# USB_interface.net
KiCad netlist of a schematic drawn in Altium Designer
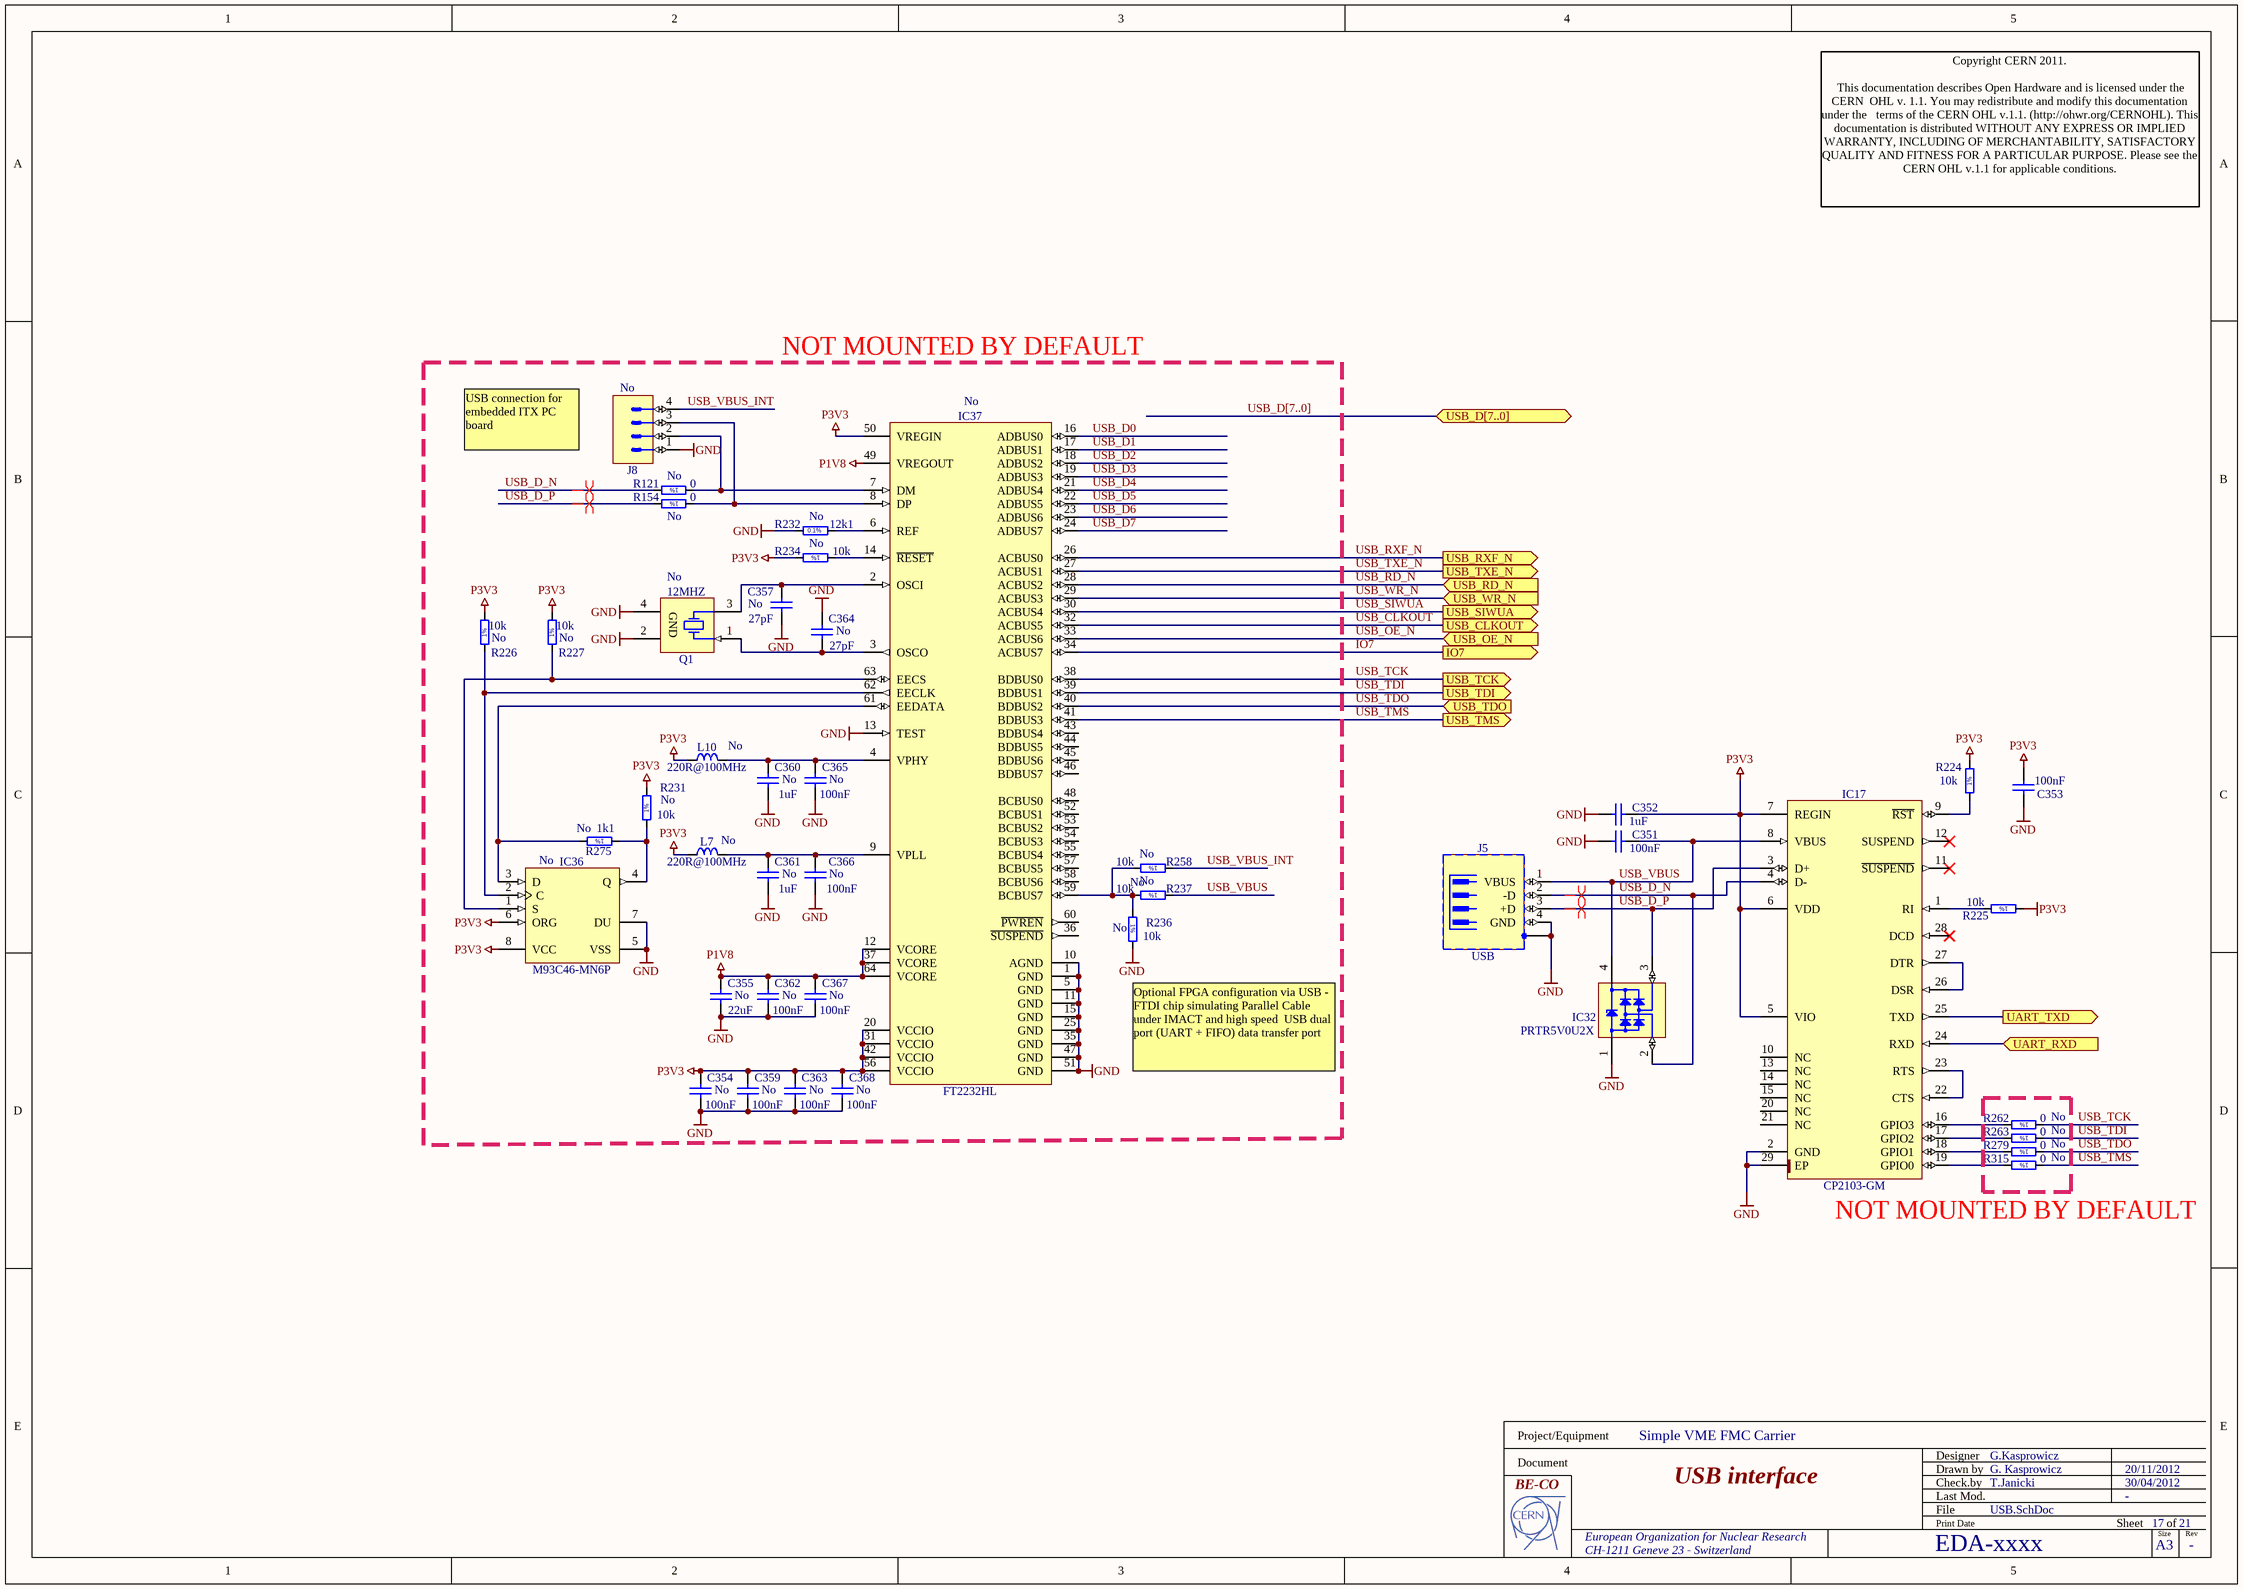
[diagram p0: USB_interface.SchDoc]

(export (version "E")
  (design (tool "Eeschema 10.0.6"))
  (components
    (comp (ref "C351")
      (value "100nF")
      (footprint "CAPC1005X55N")
      (description "Non-polarised capacitor")
      (fields
        (field (name "PART NUMBER") "CC0402_100NF_16V_10%_X7R")
        (field (name "VOLTAGE") "16V")
        (field (name "AUTHOR") "CERN DEM JLC")
      )
      (libsource (lib "Capacitors") (part "Capacitor - non polarized"))
    )
    (comp (ref "C352")
      (value "1uF")
      (footprint "CAPC1608X87N")
      (description "Non-polarised capacitor")
      (fields
        (field (name "PART NUMBER") "CC0603_1UF_16V_10%_X7R")
        (field (name "VOLTAGE") "16V")
        (field (name "AUTHOR") "CERN DEM JLC")
      )
      (libsource (lib "Capacitors") (part "Capacitor - non polarized"))
    )
    (comp (ref "C353")
      (value "100nF")
      (footprint "CAPC1005X55N")
      (description "Non-polarised capacitor")
      (fields
        (field (name "PART NUMBER") "CC0402_100NF_16V_10%_X7R")
        (field (name "VOLTAGE") "16V")
        (field (name "AUTHOR") "CERN DEM JLC")
      )
      (libsource (lib "Capacitors") (part "Capacitor - non polarized"))
    )
    (comp (ref "C354")
      (value "100nF")
      (footprint "CAPC1005X55N")
      (description "Non-polarised capacitor")
      (fields
        (field (name "PART NUMBER") "CC0402_100NF_16V_10%_X7R")
        (field (name "VOLTAGE") "16V")
        (field (name "MOUNTED") "No")
        (field (name "AUTHOR") "CERN DEM JLC")
      )
      (libsource (lib "Capacitors") (part "Capacitor - non polarized"))
    )
    (comp (ref "C355")
      (value "22uF")
      (footprint "CAPC3216X180N")
      (description "Non-polarised capacitor")
      (fields
        (field (name "PART NUMBER") "CC1206_22UF_10V_10%_X7R")
        (field (name "VOLTAGE") "10V")
        (field (name "MOUNTED") "No")
        (field (name "AUTHOR") "CERN DEM JLC")
      )
      (libsource (lib "Capacitors") (part "Capacitor - non polarized"))
    )
    (comp (ref "C357")
      (value "27pF")
      (footprint "CAPC1608X87N")
      (description "Non-polarised capacitor")
      (fields
        (field (name "PART NUMBER") "CC0603_27PF_50V_5%_NP0")
        (field (name "VOLTAGE") "50V")
        (field (name "MOUNTED") "No")
        (field (name "AUTHOR") "CERN DEM JLC")
      )
      (libsource (lib "Capacitors") (part "Capacitor - non polarized"))
    )
    (comp (ref "C359")
      (value "100nF")
      (footprint "CAPC1005X55N")
      (description "Non-polarised capacitor")
      (fields
        (field (name "PART NUMBER") "CC0402_100NF_16V_10%_X7R")
        (field (name "VOLTAGE") "16V")
        (field (name "MOUNTED") "No")
        (field (name "AUTHOR") "CERN DEM JLC")
      )
      (libsource (lib "Capacitors") (part "Capacitor - non polarized"))
    )
    (comp (ref "C360")
      (value "1uF")
      (footprint "CAPC1608X87N")
      (description "Non-polarised capacitor")
      (fields
        (field (name "PART NUMBER") "CC0603_1UF_16V_10%_X7R")
        (field (name "VOLTAGE") "16V")
        (field (name "MOUNTED") "No")
        (field (name "AUTHOR") "CERN DEM JLC")
      )
      (libsource (lib "Capacitors") (part "Capacitor - non polarized"))
    )
    (comp (ref "C361")
      (value "1uF")
      (footprint "CAPC1608X87N")
      (description "Non-polarised capacitor")
      (fields
        (field (name "PART NUMBER") "CC0603_1UF_16V_10%_X7R")
        (field (name "VOLTAGE") "16V")
        (field (name "MOUNTED") "No")
        (field (name "AUTHOR") "CERN DEM JLC")
      )
      (libsource (lib "Capacitors") (part "Capacitor - non polarized"))
    )
    (comp (ref "C362")
      (value "100nF")
      (footprint "CAPC1005X55N")
      (description "Non-polarised capacitor")
      (fields
        (field (name "PART NUMBER") "CC0402_100NF_16V_10%_X7R")
        (field (name "VOLTAGE") "16V")
        (field (name "MOUNTED") "No")
        (field (name "AUTHOR") "CERN DEM JLC")
      )
      (libsource (lib "Capacitors") (part "Capacitor - non polarized"))
    )
    (comp (ref "C363")
      (value "100nF")
      (footprint "CAPC1005X55N")
      (description "Non-polarised capacitor")
      (fields
        (field (name "PART NUMBER") "CC0402_100NF_16V_10%_X7R")
        (field (name "VOLTAGE") "16V")
        (field (name "MOUNTED") "No")
        (field (name "AUTHOR") "CERN DEM JLC")
      )
      (libsource (lib "Capacitors") (part "Capacitor - non polarized"))
    )
    (comp (ref "C364")
      (value "27pF")
      (footprint "CAPC1608X87N")
      (description "Non-polarised capacitor")
      (fields
        (field (name "PART NUMBER") "CC0603_27PF_50V_5%_NP0")
        (field (name "VOLTAGE") "50V")
        (field (name "MOUNTED") "No")
        (field (name "AUTHOR") "CERN DEM JLC")
      )
      (libsource (lib "Capacitors") (part "Capacitor - non polarized"))
    )
    (comp (ref "C365")
      (value "100nF")
      (footprint "CAPC1005X55N")
      (description "Non-polarised capacitor")
      (fields
        (field (name "PART NUMBER") "CC0402_100NF_16V_10%_X7R")
        (field (name "VOLTAGE") "16V")
        (field (name "MOUNTED") "No")
        (field (name "AUTHOR") "CERN DEM JLC")
      )
      (libsource (lib "Capacitors") (part "Capacitor - non polarized"))
    )
    (comp (ref "C366")
      (value "100nF")
      (footprint "CAPC1005X55N")
      (description "Non-polarised capacitor")
      (fields
        (field (name "PART NUMBER") "CC0402_100NF_16V_10%_X7R")
        (field (name "VOLTAGE") "16V")
        (field (name "MOUNTED") "No")
        (field (name "AUTHOR") "CERN DEM JLC")
      )
      (libsource (lib "Capacitors") (part "Capacitor - non polarized"))
    )
    (comp (ref "C367")
      (value "100nF")
      (footprint "CAPC1005X55N")
      (description "Non-polarised capacitor")
      (fields
        (field (name "PART NUMBER") "CC0402_100NF_16V_10%_X7R")
        (field (name "VOLTAGE") "16V")
        (field (name "MOUNTED") "No")
        (field (name "AUTHOR") "CERN DEM JLC")
      )
      (libsource (lib "Capacitors") (part "Capacitor - non polarized"))
    )
    (comp (ref "C368")
      (value "100nF")
      (footprint "CAPC1005X55N")
      (description "Non-polarised capacitor")
      (fields
        (field (name "PART NUMBER") "CC0402_100NF_16V_10%_X7R")
        (field (name "VOLTAGE") "16V")
        (field (name "MOUNTED") "No")
        (field (name "AUTHOR") "CERN DEM JLC")
      )
      (libsource (lib "Capacitors") (part "Capacitor - non polarized"))
    )
    (comp (ref "IC17")
      (value "CP2103-GM")
      (footprint "QFN50P500X500X100-29N-S335")
      (description "Single-Chip USB to UART Bridge")
      (fields (field (name "MANUFACTURER") "SILICON LABS") (field (name "AUTHOR") "CERN DEM JLC"))
      (libsource (lib "ICs And Semiconductors") (part "CP2103-GM"))
    )
    (comp (ref "IC32")
      (value "PRTR5V0U2X")
      (footprint "SOT190P230X110-4N")
      (description "Ultra Low Capacitance Double Rail-to-Rail ESD Protection Diode")
      (fields
        (field (name "VOLTAGE") "5.5V")
        (field (name "MANUFACTURER") "PHILIPS NXP")
        (field (name "AUTHOR") "CERN DEM JLC")
      )
      (libsource (lib "ICs And Semiconductors") (part "PRTR5V0U2X"))
    )
    (comp (ref "IC36")
      (value "M93C46-MN6P")
      (footprint "SOIC127P600X175-8N")
      (description "1Kb (x8/x16) Serial Microwire Bus EEPROM")
      (fields
        (field (name "MANUFACTURER") "ST MICROELECTRONICS")
        (field (name "MOUNTED") "No")
        (field (name "AUTHOR") "CERN DEM JLC")
      )
      (libsource (lib "ICs And Semiconductors") (part "M93C46-MN"))
    )
    (comp (ref "IC37")
      (value "FT2232HL")
      (footprint "QFP50P1200X1200X160-64N")
      (description "Dual High Speed USB to Multipurpose UART/FIFO IC")
      (fields
        (field (name "MANUFACTURER") "FUTURE TECHNOLOGY DEVICES INTERNATIONAL (FTDI)")
        (field (name "MOUNTED") "No")
        (field (name "AUTHOR") "CERN DEM JLC")
      )
      (libsource (lib "ICs And Semiconductors") (part "FT2232H"))
    )
    (comp (ref "J5")
      (value "USB")
      (footprint "TYCO_292304-1")
      (description "4 Pin + 1 Shield USB Receptacle")
      (fields
        (field (name "PART NUMBER") "TYCO_292304-1")
        (field (name "MANUFACTURER") "TYCO ELECTRONICS")
        (field (name "AUTHOR") "CERN DEM JLC")
      )
      (libsource (lib "Connectors") (part "Connector USB 4 Pin + 1Shield"))
    )
    (comp (ref "J8")
      (value "KK®")
      (footprint "MOLEX_22-04-1041")
      (description "Connector 4 Male")
      (fields
        (field (name "PART NUMBER") "MOLEX_22-04-1041")
        (field (name "MOUNTED") "No")
        (field (name "MANUFACTURER") "MOLEX")
        (field (name "AUTHOR") "CERN DEM JLC")
      )
      (libsource (lib "Connectors") (part "Connector 4 Male"))
    )
    (comp (ref "L7")
      (value "220R@100MHz")
      (footprint "INDC2012X105N")
      (description "Inductor")
      (fields
        (field (name "PART NUMBER") "IND0805_MURATA_BLM21PG221SN1D")
        (field (name "POWER") "2A")
        (field (name "MOUNTED") "No")
        (field (name "AUTHOR") "CERN DEM JLC")
      )
      (libsource (lib "Inductors & Transformers") (part "Inductor"))
    )
    (comp (ref "L10")
      (value "220R@100MHz")
      (footprint "INDC2012X105N")
      (description "Inductor")
      (fields
        (field (name "PART NUMBER") "IND0805_MURATA_BLM21PG221SN1D")
        (field (name "POWER") "2A")
        (field (name "MOUNTED") "No")
        (field (name "AUTHOR") "CERN DEM JLC")
      )
      (libsource (lib "Inductors & Transformers") (part "Inductor"))
    )
    (comp (ref "Q1")
      (value "12MHZ")
      (footprint "XTAL_ABRACON_ABM3B")
      (description "Crystal 4 pins 1=XTAL Control 2=GND3=XTAL 4=GND")
      (fields
        (field (name "PART NUMBER") "XTAL_12MHZ_ABRACON_ABM3B-12.000MHZ-B2-T")
        (field (name "MANUFACTURER") "ABRACON")
        (field (name "MOUNTED") "No")
        (field (name "AUTHOR") "CERN DEM JLC")
      )
      (libsource (lib "ICs And Semiconductors") (part "Quartz Crystal 1X 2GND 3X 4GND"))
    )
    (comp (ref "R121")
      (value "0")
      (footprint "RESC1608X55N")
      (description "Resistor - 1%")
      (fields
        (field (name "PART NUMBER") "R0603_0R_JUMPER")
        (field (name "MANUFACTURER") "GENERIC")
        (field (name "MOUNTED") "No")
        (field (name "AUTHOR") "CERN DEM JLC")
      )
      (libsource (lib "Resistors") (part "Resistor - 1%"))
    )
    (comp (ref "R154")
      (value "0")
      (footprint "RESC1608X55N")
      (description "Resistor - 1%")
      (fields
        (field (name "PART NUMBER") "R0603_0R_JUMPER")
        (field (name "MANUFACTURER") "GENERIC")
        (field (name "MOUNTED") "No")
        (field (name "AUTHOR") "CERN DEM JLC")
      )
      (libsource (lib "Resistors") (part "Resistor - 1%"))
    )
    (comp (ref "R224")
      (value "10k")
      (footprint "RESC1608X55N")
      (description "Resistor - 1%")
      (fields
        (field (name "PART NUMBER") "R0603_10K_1%_0.1W_100PPM")
        (field (name "POWER") "0.1W")
        (field (name "AUTHOR") "CERN DEM JLC")
      )
      (libsource (lib "Resistors") (part "Resistor - 1%"))
    )
    (comp (ref "R225")
      (value "10k")
      (footprint "RESC1608X55N")
      (description "Resistor - 1%")
      (fields
        (field (name "PART NUMBER") "R0603_10K_1%_0.1W_100PPM")
        (field (name "POWER") "0.1W")
        (field (name "AUTHOR") "CERN DEM JLC")
      )
      (libsource (lib "Resistors") (part "Resistor - 1%"))
    )
    (comp (ref "R226")
      (value "10k")
      (footprint "RESC1608X55N")
      (description "Resistor - 1%")
      (fields
        (field (name "PART NUMBER") "R0603_10K_1%_0.1W_100PPM")
        (field (name "POWER") "0.1W")
        (field (name "MOUNTED") "No")
        (field (name "AUTHOR") "CERN DEM JLC")
      )
      (libsource (lib "Resistors") (part "Resistor - 1%"))
    )
    (comp (ref "R227")
      (value "10k")
      (footprint "RESC1608X55N")
      (description "Resistor - 1%")
      (fields
        (field (name "PART NUMBER") "R0603_10K_1%_0.1W_100PPM")
        (field (name "POWER") "0.1W")
        (field (name "MOUNTED") "No")
        (field (name "AUTHOR") "CERN DEM JLC")
      )
      (libsource (lib "Resistors") (part "Resistor - 1%"))
    )
    (comp (ref "R231")
      (value "10k")
      (footprint "RESC1608X55N")
      (description "Resistor - 1%")
      (fields
        (field (name "PART NUMBER") "R0603_10K_1%_0.1W_100PPM")
        (field (name "POWER") "0.1W")
        (field (name "MOUNTED") "No")
        (field (name "AUTHOR") "CERN DEM JLC")
      )
      (libsource (lib "Resistors") (part "Resistor - 1%"))
    )
    (comp (ref "R232")
      (value "12k1")
      (footprint "RESC1608X55N")
      (description "Resistor - 0.1%")
      (fields
        (field (name "PART NUMBER") "R0603_12K1_0.1%_0.063W_10PPM")
        (field (name "POWER") "0.063W")
        (field (name "MOUNTED") "No")
        (field (name "AUTHOR") "CERN DEM JLC")
      )
      (libsource (lib "Resistors") (part "Resistor - 0.1%"))
    )
    (comp (ref "R234")
      (value "10k")
      (footprint "RESC1608X55N")
      (description "Resistor - 1%")
      (fields
        (field (name "PART NUMBER") "R0603_10K_1%_0.1W_100PPM")
        (field (name "POWER") "0.1W")
        (field (name "MOUNTED") "No")
        (field (name "AUTHOR") "CERN DEM JLC")
      )
      (libsource (lib "Resistors") (part "Resistor - 1%"))
    )
    (comp (ref "R236")
      (value "10k")
      (footprint "RESC1608X55N")
      (description "Resistor - 1%")
      (fields
        (field (name "PART NUMBER") "R0603_10K_1%_0.1W_100PPM")
        (field (name "POWER") "0.1W")
        (field (name "MOUNTED") "No")
        (field (name "AUTHOR") "CERN DEM JLC")
      )
      (libsource (lib "Resistors") (part "Resistor - 1%"))
    )
    (comp (ref "R237")
      (value "10k")
      (footprint "RESC1608X55N")
      (description "Resistor - 1%")
      (fields
        (field (name "PART NUMBER") "R0603_10K_1%_0.1W_100PPM")
        (field (name "POWER") "0.1W")
        (field (name "MOUNTED") "No")
        (field (name "SOCKET") "No")
        (field (name "AUTHOR") "CERN DEM JLC")
      )
      (libsource (lib "Resistors") (part "Resistor - 1%"))
    )
    (comp (ref "R258")
      (value "10k")
      (footprint "RESC1608X55N")
      (description "Resistor - 1%")
      (fields
        (field (name "PART NUMBER") "R0603_10K_1%_0.1W_100PPM")
        (field (name "POWER") "0.1W")
        (field (name "MOUNTED") "No")
        (field (name "AUTHOR") "CERN DEM JLC")
      )
      (libsource (lib "Resistors") (part "Resistor - 1%"))
    )
    (comp (ref "R262")
      (value "0")
      (footprint "RESC1608X55N")
      (description "Resistor - 1%")
      (fields
        (field (name "PART NUMBER") "R0603_0R_JUMPER")
        (field (name "MANUFACTURER") "GENERIC")
        (field (name "MOUNTED") "No")
        (field (name "AUTHOR") "CERN DEM JLC")
      )
      (libsource (lib "Resistors") (part "Resistor - 1%"))
    )
    (comp (ref "R263")
      (value "0")
      (footprint "RESC1608X55N")
      (description "Resistor - 1%")
      (fields
        (field (name "PART NUMBER") "R0603_0R_JUMPER")
        (field (name "MANUFACTURER") "GENERIC")
        (field (name "MOUNTED") "No")
        (field (name "AUTHOR") "CERN DEM JLC")
      )
      (libsource (lib "Resistors") (part "Resistor - 1%"))
    )
    (comp (ref "R275")
      (value "1k1")
      (footprint "RESC1608X55N")
      (description "Resistor - 1%")
      (fields
        (field (name "PART NUMBER") "R0603_1K1_1%_0.1W_100PPM")
        (field (name "POWER") "0.1W")
        (field (name "MOUNTED") "No")
        (field (name "AUTHOR") "CERN DEM JLC")
      )
      (libsource (lib "Resistors") (part "Resistor - 1%"))
    )
    (comp (ref "R279")
      (value "0")
      (footprint "RESC1608X55N")
      (description "Resistor - 1%")
      (fields
        (field (name "PART NUMBER") "R0603_0R_JUMPER")
        (field (name "MANUFACTURER") "GENERIC")
        (field (name "MOUNTED") "No")
        (field (name "AUTHOR") "CERN DEM JLC")
      )
      (libsource (lib "Resistors") (part "Resistor - 1%"))
    )
    (comp (ref "R315")
      (value "0")
      (footprint "RESC1608X55N")
      (description "Resistor - 1%")
      (fields
        (field (name "PART NUMBER") "R0603_0R_JUMPER")
        (field (name "MANUFACTURER") "GENERIC")
        (field (name "MOUNTED") "No")
        (field (name "AUTHOR") "CERN DEM JLC")
      )
      (libsource (lib "Resistors") (part "Resistor - 1%"))
    )
  )
  (nets
    (net (code "1") (name "/IO7") (class "Default")
      (node (ref "IC37") (pin "34") (pinfunction "ACBUS7_34") (pintype "bidirectional"))
    )
    (net (code "2") (name "/UART_RXD") (class "Default")
      (node (ref "IC17") (pin "24") (pinfunction "RXD_24") (pintype "input"))
    )
    (net (code "3") (name "/UART_TXD") (class "Default")
      (node (ref "IC17") (pin "25") (pinfunction "TXD_25") (pintype "output"))
    )
    (net (code "4") (name "/USB_CLKOUT") (class "Default")
      (node (ref "IC37") (pin "32") (pinfunction "ACBUS5_32") (pintype "bidirectional"))
    )
    (net (code "5") (name "/USB_D0") (class "Default")
      (node (ref "IC37") (pin "16") (pinfunction "ADBUS0_16") (pintype "bidirectional"))
    )
    (net (code "6") (name "/USB_D1") (class "Default")
      (node (ref "IC37") (pin "17") (pinfunction "ADBUS1_17") (pintype "bidirectional"))
    )
    (net (code "7") (name "/USB_D2") (class "Default")
      (node (ref "IC37") (pin "18") (pinfunction "ADBUS2_18") (pintype "bidirectional"))
    )
    (net (code "8") (name "/USB_D3") (class "Default")
      (node (ref "IC37") (pin "19") (pinfunction "ADBUS3_19") (pintype "bidirectional"))
    )
    (net (code "9") (name "/USB_D4") (class "Default")
      (node (ref "IC37") (pin "21") (pinfunction "ADBUS4_21") (pintype "bidirectional"))
    )
    (net (code "10") (name "/USB_D5") (class "Default")
      (node (ref "IC37") (pin "22") (pinfunction "ADBUS5_22") (pintype "bidirectional"))
    )
    (net (code "11") (name "/USB_D6") (class "Default")
      (node (ref "IC37") (pin "23") (pinfunction "ADBUS6_23") (pintype "bidirectional"))
    )
    (net (code "12") (name "/USB_D7") (class "Default")
      (node (ref "IC37") (pin "24") (pinfunction "ADBUS7_24") (pintype "bidirectional"))
    )
    (net (code "14") (name "/USB_D_N") (class "Default")
      (node (ref "IC17") (pin "4") (pinfunction "D-_4") (pintype "bidirectional"))
      (node (ref "IC32") (pin "2") (pinfunction "I/O1_2") (pintype "bidirectional"))
      (node (ref "J5") (pin "2") (pinfunction "-D_2") (pintype "bidirectional"))
      (node (ref "R121") (pin "2") (pinfunction "2_2") (pintype "passive"))
    )
    (net (code "15") (name "/USB_D_P") (class "Default")
      (node (ref "IC17") (pin "3") (pinfunction "D+_3") (pintype "bidirectional"))
      (node (ref "IC32") (pin "3") (pinfunction "I/O2_3") (pintype "bidirectional"))
      (node (ref "J5") (pin "3") (pinfunction "+D_3") (pintype "bidirectional"))
      (node (ref "R154") (pin "2") (pinfunction "2_2") (pintype "passive"))
    )
    (net (code "16") (name "/USB_OE_N") (class "Default")
      (node (ref "IC37") (pin "33") (pinfunction "ACBUS6_33") (pintype "bidirectional"))
    )
    (net (code "17") (name "/USB_RD_N") (class "Default")
      (node (ref "IC37") (pin "28") (pinfunction "ACBUS2_28") (pintype "bidirectional"))
    )
    (net (code "18") (name "/USB_RXF_N") (class "Default")
      (node (ref "IC37") (pin "26") (pinfunction "ACBUS0_26") (pintype "bidirectional"))
    )
    (net (code "19") (name "/USB_SIWUA") (class "Default")
      (node (ref "IC37") (pin "30") (pinfunction "ACBUS4_30") (pintype "bidirectional"))
    )
    (net (code "20") (name "/USB_TCK") (class "Default")
      (node (ref "IC37") (pin "38") (pinfunction "BDBUS0_38") (pintype "bidirectional"))
      (node (ref "R262") (pin "1") (pinfunction "1_1") (pintype "passive"))
    )
    (net (code "21") (name "/USB_TDI") (class "Default")
      (node (ref "IC37") (pin "39") (pinfunction "BDBUS1_39") (pintype "bidirectional"))
      (node (ref "R263") (pin "1") (pinfunction "1_1") (pintype "passive"))
    )
    (net (code "22") (name "/USB_TDO") (class "Default")
      (node (ref "IC37") (pin "40") (pinfunction "BDBUS2_40") (pintype "bidirectional"))
      (node (ref "R279") (pin "1") (pinfunction "1_1") (pintype "passive"))
    )
    (net (code "23") (name "/USB_TMS") (class "Default")
      (node (ref "IC37") (pin "41") (pinfunction "BDBUS3_41") (pintype "bidirectional"))
      (node (ref "R315") (pin "1") (pinfunction "1_1") (pintype "passive"))
    )
    (net (code "24") (name "/USB_TXE_N") (class "Default")
      (node (ref "IC37") (pin "27") (pinfunction "ACBUS1_27") (pintype "bidirectional"))
    )
    (net (code "25") (name "/USB_VBUS") (class "Default")
      (node (ref "C351") (pin "1") (pinfunction "1_1") (pintype "passive"))
      (node (ref "IC17") (pin "8") (pinfunction "VBUS_8") (pintype "input"))
      (node (ref "IC32") (pin "4") (pinfunction "VCC_4") (pintype "power_in"))
      (node (ref "J5") (pin "1") (pinfunction "VBUS_1") (pintype "bidirectional"))
      (node (ref "R237") (pin "1") (pinfunction "1_1") (pintype "passive"))
    )
    (net (code "26") (name "/USB_VBUS_INT") (class "Default")
      (node (ref "J8") (pin "4") (pinfunction "4_4") (pintype "bidirectional"))
      (node (ref "R258") (pin "1") (pinfunction "1_1") (pintype "passive"))
    )
    (net (code "27") (name "/USB_WR_N") (class "Default")
      (node (ref "IC37") (pin "29") (pinfunction "ACBUS3_29") (pintype "bidirectional"))
    )
    (net (code "28") (name "GND") (class "Default")
      (node (ref "C351") (pin "2") (pinfunction "2_2") (pintype "passive"))
      (node (ref "C352") (pin "2") (pinfunction "2_2") (pintype "passive"))
      (node (ref "C353") (pin "2") (pinfunction "2_2") (pintype "passive"))
      (node (ref "C354") (pin "2") (pinfunction "2_2") (pintype "passive"))
      (node (ref "C355") (pin "1") (pinfunction "1_1") (pintype "passive"))
      (node (ref "C357") (pin "1") (pinfunction "1_1") (pintype "passive"))
      (node (ref "C359") (pin "2") (pinfunction "2_2") (pintype "passive"))
      (node (ref "C360") (pin "1") (pinfunction "1_1") (pintype "passive"))
      (node (ref "C361") (pin "1") (pinfunction "1_1") (pintype "passive"))
      (node (ref "C362") (pin "2") (pinfunction "2_2") (pintype "passive"))
      (node (ref "C363") (pin "2") (pinfunction "2_2") (pintype "passive"))
      (node (ref "C364") (pin "1") (pinfunction "1_1") (pintype "passive"))
      (node (ref "C365") (pin "2") (pinfunction "2_2") (pintype "passive"))
      (node (ref "C366") (pin "2") (pinfunction "2_2") (pintype "passive"))
      (node (ref "C367") (pin "2") (pinfunction "2_2") (pintype "passive"))
      (node (ref "C368") (pin "2") (pinfunction "2_2") (pintype "passive"))
      (node (ref "IC17") (pin "2") (pinfunction "GND_2") (pintype "power_in"))
      (node (ref "IC17") (pin "29") (pinfunction "EP_29") (pintype "power_in"))
      (node (ref "IC32") (pin "1") (pinfunction "GND_1") (pintype "power_in"))
      (node (ref "IC36") (pin "5") (pinfunction "VSS_5") (pintype "power_in"))
      (node (ref "IC36") (pin "7") (pinfunction "DU_7") (pintype "passive"))
      (node (ref "IC37") (pin "1") (pinfunction "GND_1") (pintype "power_in"))
      (node (ref "IC37") (pin "10") (pinfunction "AGND_10") (pintype "power_in"))
      (node (ref "IC37") (pin "11") (pinfunction "GND_11") (pintype "power_in"))
      (node (ref "IC37") (pin "13") (pinfunction "TEST_13") (pintype "input"))
      (node (ref "IC37") (pin "15") (pinfunction "GND_15") (pintype "power_in"))
      (node (ref "IC37") (pin "25") (pinfunction "GND_25") (pintype "power_in"))
      (node (ref "IC37") (pin "35") (pinfunction "GND_35") (pintype "power_in"))
      (node (ref "IC37") (pin "47") (pinfunction "GND_47") (pintype "power_in"))
      (node (ref "IC37") (pin "5") (pinfunction "GND_5") (pintype "power_in"))
      (node (ref "IC37") (pin "51") (pinfunction "GND_51") (pintype "power_in"))
      (node (ref "J5") (pin "4") (pinfunction "GND_4") (pintype "bidirectional"))
      (node (ref "J5") (pin "5") (pinfunction "SH_5") (pintype "power_in"))
      (node (ref "J8") (pin "1") (pinfunction "1_1") (pintype "bidirectional"))
      (node (ref "Q1") (pin "2") (pinfunction "GND_2") (pintype "power_in"))
      (node (ref "Q1") (pin "4") (pinfunction "GND_4") (pintype "power_in"))
      (node (ref "R232") (pin "1") (pinfunction "1_1") (pintype "passive"))
      (node (ref "R236") (pin "2") (pinfunction "2_2") (pintype "passive"))
    )
    (net (code "29") (name "Net-(IC17-CTS)") (class "Default")
      (node (ref "IC17") (pin "22") (pinfunction "CTS_22") (pintype "input"))
      (node (ref "IC17") (pin "23") (pinfunction "RTS_23") (pintype "output"))
    )
    (net (code "30") (name "Net-(IC17-DSR)") (class "Default")
      (node (ref "IC17") (pin "26") (pinfunction "DSR_26") (pintype "input"))
      (node (ref "IC17") (pin "27") (pinfunction "DTR_27") (pintype "output"))
    )
    (net (code "31") (name "Net-(IC17-GPIO0)") (class "Default")
      (node (ref "IC17") (pin "19") (pinfunction "GPIO0_19") (pintype "bidirectional"))
      (node (ref "R315") (pin "2") (pinfunction "2_2") (pintype "passive"))
    )
    (net (code "32") (name "Net-(IC17-GPIO1)") (class "Default")
      (node (ref "IC17") (pin "18") (pinfunction "GPIO1_18") (pintype "bidirectional"))
      (node (ref "R279") (pin "2") (pinfunction "2_2") (pintype "passive"))
    )
    (net (code "33") (name "Net-(IC17-GPIO2)") (class "Default")
      (node (ref "IC17") (pin "17") (pinfunction "GPIO2_17") (pintype "bidirectional"))
      (node (ref "R263") (pin "2") (pinfunction "2_2") (pintype "passive"))
    )
    (net (code "34") (name "Net-(IC17-GPIO3)") (class "Default")
      (node (ref "IC17") (pin "16") (pinfunction "GPIO3_16") (pintype "bidirectional"))
      (node (ref "R262") (pin "2") (pinfunction "2_2") (pintype "passive"))
    )
    (net (code "35") (name "Net-(IC17-RI)") (class "Default")
      (node (ref "IC17") (pin "1") (pinfunction "RI_1") (pintype "input"))
      (node (ref "R225") (pin "2") (pinfunction "2_2") (pintype "passive"))
    )
    (net (code "36") (name "Net-(IC17-~{RST})") (class "Default")
      (node (ref "IC17") (pin "9") (pinfunction "~{RST}_9") (pintype "bidirectional"))
      (node (ref "R224") (pin "1") (pinfunction "1_1") (pintype "passive"))
    )
    (net (code "37") (name "Net-(IC36-C)") (class "Default")
      (node (ref "IC36") (pin "2") (pinfunction "C_2") (pintype "input"))
      (node (ref "IC37") (pin "62") (pinfunction "EECLK_62") (pintype "output"))
      (node (ref "R226") (pin "1") (pinfunction "1_1") (pintype "passive"))
    )
    (net (code "38") (name "Net-(IC36-D)") (class "Default")
      (node (ref "IC36") (pin "3") (pinfunction "D_3") (pintype "input"))
      (node (ref "IC37") (pin "61") (pinfunction "EEDATA_61") (pintype "bidirectional"))
      (node (ref "R275") (pin "2") (pinfunction "2_2") (pintype "passive"))
    )
    (net (code "39") (name "Net-(IC36-Q)") (class "Default")
      (node (ref "IC36") (pin "4") (pinfunction "Q_4") (pintype "output"))
      (node (ref "R231") (pin "1") (pinfunction "1_1") (pintype "passive"))
      (node (ref "R275") (pin "1") (pinfunction "1_1") (pintype "passive"))
    )
    (net (code "40") (name "Net-(IC36-S)") (class "Default")
      (node (ref "IC36") (pin "1") (pinfunction "S_1") (pintype "input"))
      (node (ref "IC37") (pin "63") (pinfunction "EECS_63") (pintype "bidirectional"))
      (node (ref "R227") (pin "1") (pinfunction "1_1") (pintype "passive"))
    )
    (net (code "41") (name "Net-(IC37-BCBUS7)") (class "Default")
      (node (ref "IC37") (pin "59") (pinfunction "BCBUS7_59") (pintype "bidirectional"))
      (node (ref "R236") (pin "1") (pinfunction "1_1") (pintype "passive"))
      (node (ref "R237") (pin "2") (pinfunction "2_2") (pintype "passive"))
      (node (ref "R258") (pin "2") (pinfunction "2_2") (pintype "passive"))
    )
    (net (code "42") (name "Net-(IC37-DM)") (class "Default")
      (node (ref "IC37") (pin "7") (pinfunction "DM_7") (pintype "input"))
      (node (ref "J8") (pin "2") (pinfunction "2_2") (pintype "bidirectional"))
      (node (ref "R121") (pin "1") (pinfunction "1_1") (pintype "passive"))
    )
    (net (code "43") (name "Net-(IC37-DP)") (class "Default")
      (node (ref "IC37") (pin "8") (pinfunction "DP_8") (pintype "input"))
      (node (ref "J8") (pin "3") (pinfunction "3_3") (pintype "bidirectional"))
      (node (ref "R154") (pin "1") (pinfunction "1_1") (pintype "passive"))
    )
    (net (code "44") (name "Net-(IC37-OSCI)") (class "Default")
      (node (ref "C357") (pin "2") (pinfunction "2_2") (pintype "passive"))
      (node (ref "IC37") (pin "2") (pinfunction "OSCI_2") (pintype "input"))
      (node (ref "Q1") (pin "3") (pinfunction "X_3") (pintype "power_in"))
    )
    (net (code "45") (name "Net-(IC37-OSCO)") (class "Default")
      (node (ref "C364") (pin "2") (pinfunction "2_2") (pintype "passive"))
      (node (ref "IC37") (pin "3") (pinfunction "OSCO_3") (pintype "output"))
      (node (ref "Q1") (pin "1") (pinfunction "X_1") (pintype "input"))
    )
    (net (code "46") (name "Net-(IC37-REF)") (class "Default")
      (node (ref "IC37") (pin "6") (pinfunction "REF_6") (pintype "input"))
      (node (ref "R232") (pin "2") (pinfunction "2_2") (pintype "passive"))
    )
    (net (code "47") (name "Net-(IC37-VPHY)") (class "Default")
      (node (ref "C360") (pin "2") (pinfunction "2_2") (pintype "passive"))
      (node (ref "C365") (pin "1") (pinfunction "1_1") (pintype "passive"))
      (node (ref "IC37") (pin "4") (pinfunction "VPHY_4") (pintype "power_in"))
      (node (ref "L10") (pin "2") (pinfunction "2_2") (pintype "passive"))
    )
    (net (code "48") (name "Net-(IC37-VPLL)") (class "Default")
      (node (ref "C361") (pin "2") (pinfunction "2_2") (pintype "passive"))
      (node (ref "C366") (pin "1") (pinfunction "1_1") (pintype "passive"))
      (node (ref "IC37") (pin "9") (pinfunction "VPLL_9") (pintype "power_in"))
      (node (ref "L7") (pin "2") (pinfunction "2_2") (pintype "passive"))
    )
    (net (code "49") (name "Net-(IC37-~{RESET})") (class "Default")
      (node (ref "IC37") (pin "14") (pinfunction "~{RESET}_14") (pintype "input"))
      (node (ref "R234") (pin "1") (pinfunction "1_1") (pintype "passive"))
    )
    (net (code "50") (name "P1V8") (class "Default")
      (node (ref "C355") (pin "2") (pinfunction "2_2") (pintype "passive"))
      (node (ref "C362") (pin "1") (pinfunction "1_1") (pintype "passive"))
      (node (ref "C367") (pin "1") (pinfunction "1_1") (pintype "passive"))
      (node (ref "IC37") (pin "12") (pinfunction "VCORE_12") (pintype "power_in"))
      (node (ref "IC37") (pin "37") (pinfunction "VCORE_37") (pintype "power_in"))
      (node (ref "IC37") (pin "49") (pinfunction "VREGOUT_49") (pintype "power_in"))
      (node (ref "IC37") (pin "64") (pinfunction "VCORE_64") (pintype "power_in"))
    )
    (net (code "51") (name "P3V3") (class "Default")
      (node (ref "C352") (pin "1") (pinfunction "1_1") (pintype "passive"))
      (node (ref "C353") (pin "1") (pinfunction "1_1") (pintype "passive"))
      (node (ref "C354") (pin "1") (pinfunction "1_1") (pintype "passive"))
      (node (ref "C359") (pin "1") (pinfunction "1_1") (pintype "passive"))
      (node (ref "C363") (pin "1") (pinfunction "1_1") (pintype "passive"))
      (node (ref "C368") (pin "1") (pinfunction "1_1") (pintype "passive"))
      (node (ref "IC17") (pin "5") (pinfunction "VIO_5") (pintype "power_in"))
      (node (ref "IC17") (pin "6") (pinfunction "VDD_6") (pintype "power_in"))
      (node (ref "IC17") (pin "7") (pinfunction "REGIN_7") (pintype "power_in"))
      (node (ref "IC36") (pin "6") (pinfunction "ORG_6") (pintype "input"))
      (node (ref "IC36") (pin "8") (pinfunction "VCC_8") (pintype "power_in"))
      (node (ref "IC37") (pin "20") (pinfunction "VCCIO_20") (pintype "power_in"))
      (node (ref "IC37") (pin "31") (pinfunction "VCCIO_31") (pintype "power_in"))
      (node (ref "IC37") (pin "42") (pinfunction "VCCIO_42") (pintype "power_in"))
      (node (ref "IC37") (pin "50") (pinfunction "VREGIN_50") (pintype "power_in"))
      (node (ref "IC37") (pin "56") (pinfunction "VCCIO_56") (pintype "power_in"))
      (node (ref "L10") (pin "1") (pinfunction "1_1") (pintype "passive"))
      (node (ref "L7") (pin "1") (pinfunction "1_1") (pintype "passive"))
      (node (ref "R224") (pin "2") (pinfunction "2_2") (pintype "passive"))
      (node (ref "R225") (pin "1") (pinfunction "1_1") (pintype "passive"))
      (node (ref "R226") (pin "2") (pinfunction "2_2") (pintype "passive"))
      (node (ref "R227") (pin "2") (pinfunction "2_2") (pintype "passive"))
      (node (ref "R231") (pin "2") (pinfunction "2_2") (pintype "passive"))
      (node (ref "R234") (pin "2") (pinfunction "2_2") (pintype "passive"))
    )
    (net (code "52") (name "unconnected-(IC17-DCD-Pad28)") (class "Default")
      (node (ref "IC17") (pin "28") (pinfunction "DCD_28") (pintype "input+no_connect"))
    )
    (net (code "53") (name "unconnected-(IC17-NC-Pad10)") (class "Default")
      (node (ref "IC17") (pin "10") (pinfunction "NC_10") (pintype "passive"))
    )
    (net (code "54") (name "unconnected-(IC17-NC-Pad13)") (class "Default")
      (node (ref "IC17") (pin "13") (pinfunction "NC_13") (pintype "passive"))
    )
    (net (code "55") (name "unconnected-(IC17-NC-Pad14)") (class "Default")
      (node (ref "IC17") (pin "14") (pinfunction "NC_14") (pintype "passive"))
    )
    (net (code "56") (name "unconnected-(IC17-NC-Pad15)") (class "Default")
      (node (ref "IC17") (pin "15") (pinfunction "NC_15") (pintype "passive"))
    )
    (net (code "57") (name "unconnected-(IC17-NC-Pad20)") (class "Default")
      (node (ref "IC17") (pin "20") (pinfunction "NC_20") (pintype "passive"))
    )
    (net (code "58") (name "unconnected-(IC17-NC-Pad21)") (class "Default")
      (node (ref "IC17") (pin "21") (pinfunction "NC_21") (pintype "passive"))
    )
    (net (code "59") (name "unconnected-(IC17-SUSPEND-Pad12)") (class "Default")
      (node (ref "IC17") (pin "12") (pinfunction "SUSPEND_12") (pintype "output+no_connect"))
    )
    (net (code "60") (name "unconnected-(IC17-~{SUSPEND}-Pad11)") (class "Default")
      (node (ref "IC17") (pin "11") (pinfunction "~{SUSPEND}_11") (pintype "output+no_connect"))
    )
    (net (code "61") (name "unconnected-(IC37-BCBUS0-Pad48)") (class "Default")
      (node (ref "IC37") (pin "48") (pinfunction "BCBUS0_48") (pintype "bidirectional"))
    )
    (net (code "62") (name "unconnected-(IC37-BCBUS1-Pad52)") (class "Default")
      (node (ref "IC37") (pin "52") (pinfunction "BCBUS1_52") (pintype "bidirectional"))
    )
    (net (code "63") (name "unconnected-(IC37-BCBUS2-Pad53)") (class "Default")
      (node (ref "IC37") (pin "53") (pinfunction "BCBUS2_53") (pintype "bidirectional"))
    )
    (net (code "64") (name "unconnected-(IC37-BCBUS3-Pad54)") (class "Default")
      (node (ref "IC37") (pin "54") (pinfunction "BCBUS3_54") (pintype "bidirectional"))
    )
    (net (code "65") (name "unconnected-(IC37-BCBUS4-Pad55)") (class "Default")
      (node (ref "IC37") (pin "55") (pinfunction "BCBUS4_55") (pintype "bidirectional"))
    )
    (net (code "66") (name "unconnected-(IC37-BCBUS5-Pad57)") (class "Default")
      (node (ref "IC37") (pin "57") (pinfunction "BCBUS5_57") (pintype "bidirectional"))
    )
    (net (code "67") (name "unconnected-(IC37-BCBUS6-Pad58)") (class "Default")
      (node (ref "IC37") (pin "58") (pinfunction "BCBUS6_58") (pintype "bidirectional"))
    )
    (net (code "68") (name "unconnected-(IC37-BDBUS4-Pad43)") (class "Default")
      (node (ref "IC37") (pin "43") (pinfunction "BDBUS4_43") (pintype "bidirectional"))
    )
    (net (code "69") (name "unconnected-(IC37-BDBUS5-Pad44)") (class "Default")
      (node (ref "IC37") (pin "44") (pinfunction "BDBUS5_44") (pintype "bidirectional"))
    )
    (net (code "70") (name "unconnected-(IC37-BDBUS6-Pad45)") (class "Default")
      (node (ref "IC37") (pin "45") (pinfunction "BDBUS6_45") (pintype "bidirectional"))
    )
    (net (code "71") (name "unconnected-(IC37-BDBUS7-Pad46)") (class "Default")
      (node (ref "IC37") (pin "46") (pinfunction "BDBUS7_46") (pintype "bidirectional"))
    )
    (net (code "72") (name "unconnected-(IC37-~{PWREN}-Pad60)") (class "Default")
      (node (ref "IC37") (pin "60") (pinfunction "~{PWREN}_60") (pintype "output"))
    )
    (net (code "73") (name "unconnected-(IC37-~{SUSPEND}-Pad36)") (class "Default")
      (node (ref "IC37") (pin "36") (pinfunction "~{SUSPEND}_36") (pintype "output"))
    )
  )
)
